# Flash.net
KiCad netlist of a schematic drawn in Altium Designer
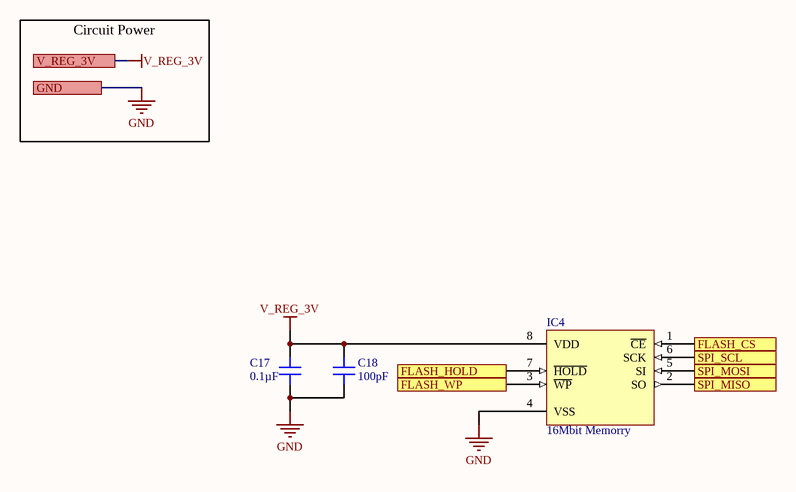
[diagram p0: Flash.SchDoc]

(export (version "E")
  (design (tool "Eeschema 10.0.6"))
  (components
    (comp (ref "C17")
      (value "0.1µF")
      (footprint "CAP 0402_1005")
      (description "CAP CER 0.1UF 16V X7R 0402")
      (fields (field (name "MANUFACTURER") "KEMET") (field (name "VOLTAGE") "16V"))
      (libsource (lib "MVVVMAltiumDatabase") (part "Capacitor"))
    )
    (comp (ref "C18")
      (value "100pF")
      (footprint "CAP 0402_1005")
      (description "CAP CER 100PF 16V C0G/NP0 0402")
      (fields (field (name "MANUFACTURER") "KEMET") (field (name "VOLTAGE") "16V"))
      (libsource (lib "MVVVMAltiumDatabase") (part "Capacitor"))
    )
    (comp (ref "IC4")
      (value "16Mbit Memorry")
      (footprint "MICROCHIP SOIC-8 150mil Wide")
      (description "IC FLASH 4MBIT SPI 40MHZ 8SOIC")
      (fields (field (name "MANUFACTURER") "Microchip Technology"))
      (libsource (lib "MVVVMAltiumDatabase") (part "MICROCHIP FLASH SPI 8PIN"))
    )
  )
  (nets
    (net (code "1") (name "/FLASH_CS") (class "Default")
      (node (ref "IC4") (pin "1") (pinfunction "~{CE}_1") (pintype "input"))
    )
    (net (code "2") (name "/FLASH_HOLD") (class "Default")
      (node (ref "IC4") (pin "7") (pinfunction "~{HOLD}_7") (pintype "input"))
    )
    (net (code "3") (name "/FLASH_WP") (class "Default")
      (node (ref "IC4") (pin "3") (pinfunction "~{WP}_3") (pintype "input"))
    )
    (net (code "4") (name "/SPI_MISO") (class "Default")
      (node (ref "IC4") (pin "2") (pinfunction "SO_2") (pintype "output"))
    )
    (net (code "5") (name "/SPI_MOSI") (class "Default")
      (node (ref "IC4") (pin "5") (pinfunction "SI_5") (pintype "input"))
    )
    (net (code "6") (name "/SPI_SCL") (class "Default")
      (node (ref "IC4") (pin "6") (pinfunction "SCK_6") (pintype "input"))
    )
    (net (code "7") (name "GND") (class "Default")
      (node (ref "C17") (pin "1") (pinfunction "1_1") (pintype "passive"))
      (node (ref "C18") (pin "1") (pinfunction "1_1") (pintype "passive"))
      (node (ref "IC4") (pin "4") (pinfunction "VSS_4") (pintype "passive"))
    )
    (net (code "8") (name "V_REG_3V") (class "Default")
      (node (ref "C17") (pin "2") (pinfunction "2_2") (pintype "passive"))
      (node (ref "C18") (pin "2") (pinfunction "2_2") (pintype "passive"))
      (node (ref "IC4") (pin "8") (pinfunction "VDD_8") (pintype "passive"))
    )
  )
)
